# type-c.net
KiCad netlist of a schematic drawn in Altium Designer
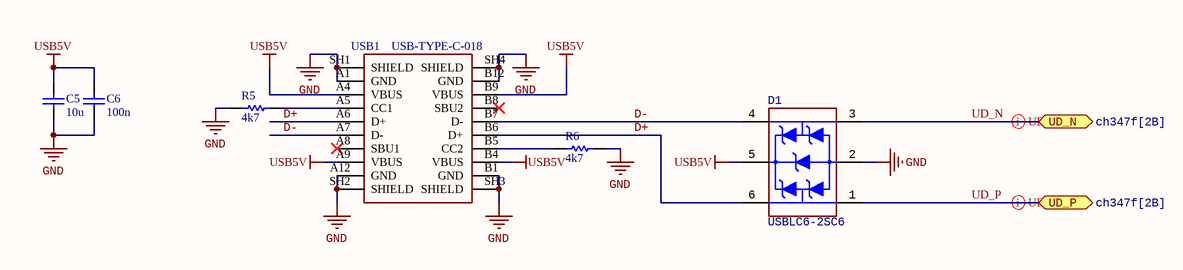
[diagram p0: type-c.SchDoc]

(export (version "E")
  (design (tool "Eeschema 10.0.6"))
  (components
    (comp (ref "C5")
      (value "10u")
      (footprint "CAPC160X80X90L30N")
      (fields
        (field (name "MPN") "TCC0603X5R106K100CT")
        (field (name "MANUFACTURER") "CCTC(三环)")
        (field (name "Comment") "Capacitor")
      )
      (libsource (lib "std_lib") (part "Capacitor"))
    )
    (comp (ref "C6")
      (value "100n")
      (footprint "CAPC100X50X55L25N")
      (fields
        (field (name "MPN") "TCC0402X5R104M250AT")
        (field (name "MANUFACTURER") "CCTC(三环)")
        (field (name "Comment") "Capacitor")
      )
      (libsource (lib "std_lib") (part "Capacitor"))
    )
    (comp (ref "D1")
      (value "USBLC6-2SC6")
      (footprint "fp-0018")
      (description "15V 6V SOT-23-6 Electrostatic and Surge Protection (TVS/ESD) ROHS")
      (fields (field (name "MANUFACTURER") "UMW"))
      (libsource (lib "std-lib") (part "sym-0030"))
    )
    (comp (ref "R5")
      (value "4k7")
      (footprint "RESC100X50X35L25N")
      (fields
        (field (name "MPN") "RTT02472JTH")
        (field (name "MANUFACTURER") "RALEC(旺诠)")
        (field (name "Comment") "Resistor")
      )
      (libsource (lib "std_lib") (part "Resistor"))
    )
    (comp (ref "R6")
      (value "4k7")
      (footprint "RESC100X50X35L25N")
      (fields
        (field (name "MPN") "RTT02472JTH")
        (field (name "MANUFACTURER") "RALEC(旺诠)")
        (field (name "Comment") "Resistor")
      )
      (libsource (lib "std_lib") (part "Resistor"))
    )
    (comp (ref "USB1")
      (value "USB-TYPE-C-018")
      (footprint "footprints:USB-TYPE-C-018")
      (libsource (lib "Sch") (part "USB-TYPE-C-018"))
    )
  )
  (nets
    (net (code "1") (name "/D+") (class "Default")
      (node (ref "D1") (pin "6") (pinfunction "6_6") (pintype "passive"))
      (node (ref "USB1") (pin "A6") (pinfunction "D+_A6") (pintype "passive"))
      (node (ref "USB1") (pin "B6") (pinfunction "D+_B6") (pintype "passive"))
    )
    (net (code "2") (name "/D-") (class "Default")
      (node (ref "D1") (pin "4") (pinfunction "4_4") (pintype "passive"))
      (node (ref "USB1") (pin "A7") (pinfunction "D-_A7") (pintype "passive"))
      (node (ref "USB1") (pin "B7") (pinfunction "D-_B7") (pintype "passive"))
    )
    (net (code "3") (name "/UD_N") (class "Default")
      (node (ref "D1") (pin "3") (pinfunction "3_3") (pintype "passive"))
    )
    (net (code "4") (name "/UD_P") (class "Default")
      (node (ref "D1") (pin "1") (pinfunction "1_1") (pintype "passive"))
    )
    (net (code "5") (name "GND") (class "Default")
      (node (ref "C5") (pin "1") (pinfunction "1_1") (pintype "passive"))
      (node (ref "C6") (pin "1") (pinfunction "1_1") (pintype "passive"))
      (node (ref "D1") (pin "2") (pinfunction "2_2") (pintype "passive"))
      (node (ref "R5") (pin "2") (pinfunction "2_2") (pintype "passive"))
      (node (ref "R6") (pin "1") (pinfunction "1_1") (pintype "passive"))
      (node (ref "USB1") (pin "A1") (pinfunction "GND_A1") (pintype "passive"))
      (node (ref "USB1") (pin "A12") (pinfunction "GND_A12") (pintype "passive"))
      (node (ref "USB1") (pin "B1") (pinfunction "GND_B1") (pintype "passive"))
      (node (ref "USB1") (pin "B12") (pinfunction "GND_B12") (pintype "passive"))
      (node (ref "USB1") (pin "SH1") (pinfunction "SHIELD_SH1") (pintype "passive"))
      (node (ref "USB1") (pin "SH2") (pinfunction "SHIELD_SH2") (pintype "passive"))
      (node (ref "USB1") (pin "SH3") (pinfunction "SHIELD_SH3") (pintype "passive"))
      (node (ref "USB1") (pin "SH4") (pinfunction "SHIELD_SH4") (pintype "passive"))
    )
    (net (code "6") (name "Net-(USB1-CC1)") (class "Default")
      (node (ref "R5") (pin "1") (pinfunction "1_1") (pintype "passive"))
      (node (ref "USB1") (pin "A5") (pinfunction "CC1_A5") (pintype "passive"))
    )
    (net (code "7") (name "Net-(USB1-CC2)") (class "Default")
      (node (ref "R6") (pin "2") (pinfunction "2_2") (pintype "passive"))
      (node (ref "USB1") (pin "B5") (pinfunction "CC2_B5") (pintype "passive"))
    )
    (net (code "8") (name "USB5V") (class "Default")
      (node (ref "C5") (pin "2") (pinfunction "2_2") (pintype "passive"))
      (node (ref "C6") (pin "2") (pinfunction "2_2") (pintype "passive"))
      (node (ref "D1") (pin "5") (pinfunction "5_5") (pintype "passive"))
      (node (ref "USB1") (pin "A4") (pinfunction "VBUS_A4") (pintype "passive"))
      (node (ref "USB1") (pin "A9") (pinfunction "VBUS_A9") (pintype "passive"))
      (node (ref "USB1") (pin "B4") (pinfunction "VBUS_B4") (pintype "passive"))
      (node (ref "USB1") (pin "B9") (pinfunction "VBUS_B9") (pintype "passive"))
    )
    (net (code "9") (name "unconnected-(USB1-SBU1-PadA8)") (class "Default")
      (node (ref "USB1") (pin "A8") (pinfunction "SBU1_A8") (pintype "passive+no_connect"))
    )
    (net (code "10") (name "unconnected-(USB1-SBU2-PadB8)") (class "Default")
      (node (ref "USB1") (pin "B8") (pinfunction "SBU2_B8") (pintype "passive+no_connect"))
    )
  )
)
